# Sheet1.net
KiCad netlist of a schematic drawn in Altium Designer
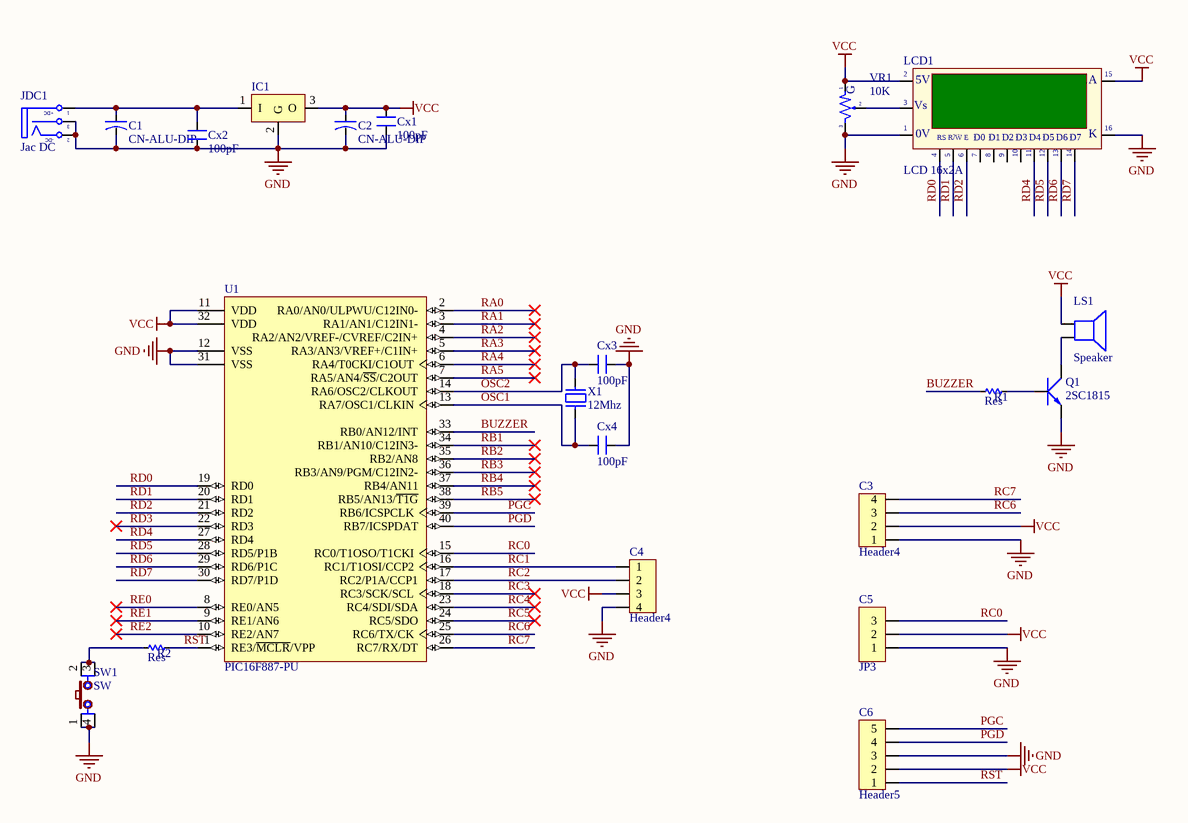
[diagram p0: Sheet1.schdoc]

(export (version "E")
  (design (tool "Eeschema 10.0.6"))
  (components
    (comp (ref "C1")
      (value "CN-ALU-DIP")
      (footprint "CA-ALU-10BL")
      (description "Capacitor (Semiconductor SIM Model)")
      (fields (field (name "PUBLISHER") "Altium Limited"))
      (libsource (lib "Thư Viện Altium FULL HD") (part "CN-ALU-DIP"))
    )
    (comp (ref "C2")
      (value "CN-ALU-DIP")
      (footprint "CA-ALU-10BL")
      (description "Capacitor (Semiconductor SIM Model)")
      (fields (field (name "PUBLISHER") "Altium Limited"))
      (libsource (lib "Thư Viện Altium FULL HD") (part "CN-ALU-DIP"))
    )
    (comp (ref "C3")
      (value "Header4")
      (footprint "Header4")
      (description "Header IDC, 4 x 1 Pin Vertical 2.54mm Pitch (Non-Boxed, Male)")
      (fields
        (field (name "MANUFACTURER") "Würth Elektronik eiSos GmbH")
        (field (name "PARTNO") "613002143121")
        (field (name "CREATED BY") "Karrer Zheng")
      )
      (libsource (lib "Thư Viện Altium FULL HD") (part "Header4"))
    )
    (comp (ref "C4")
      (value "Header4")
      (footprint "Header4")
      (description "Header IDC, 4 x 1 Pin Vertical 2.54mm Pitch (Non-Boxed, Male)")
      (fields
        (field (name "MANUFACTURER") "Würth Elektronik eiSos GmbH")
        (field (name "PARTNO") "613002143121")
        (field (name "CREATED BY") "Karrer Zheng")
      )
      (libsource (lib "") (part "Header4_1"))
    )
    (comp (ref "C5")
      (value "JP3")
      (footprint "JP3-D1T")
      (description "WR-PHD 2.54 mm Angled Socket Header")
      (fields
        (field (name "MANUFACTURER") "Würth Elektronik eiSos GmbH")
        (field (name "PARTNO") "613003143121")
        (field (name "CREATED BY") "Karrer Zheng")
      )
      (libsource (lib "Thư Viện Altium FULL HD") (part "JP3"))
    )
    (comp (ref "C6")
      (value "Header5")
      (footprint "Header5")
      (description "Header IDC, 5 x 1 Pin Vertical 2.54mm Pitch (Non-Boxed, Male)")
      (fields
        (field (name "MANUFACTURER") "Würth Elektronik eiSos GmbH")
        (field (name "PARTNO") "613002143121")
        (field (name "CREATED BY") "Karrer Zheng")
      )
      (libsource (lib "Thư Viện Altium FULL HD") (part "Header5"))
    )
    (comp (ref "Cx1")
      (value "100pF")
      (footprint "CN1.5")
      (libsource (lib "Thư Viện Altium FULL HD") (part "CN"))
    )
    (comp (ref "Cx2")
      (value "100pF")
      (footprint "CN1.5")
      (libsource (lib "Thư Viện Altium FULL HD") (part "CN"))
    )
    (comp (ref "Cx3")
      (value "100pF")
      (footprint "CN2.5")
      (libsource (lib "Thư Viện Altium FULL HD") (part "CN"))
    )
    (comp (ref "Cx4")
      (value "100pF")
      (footprint "CN2.5")
      (libsource (lib "Thư Viện Altium FULL HD") (part "CN"))
    )
    (comp (ref "IC1")
      (value "LM78xx")
      (footprint "TO220-123")
      (description "Positive Voltage Regulator")
      (fields (field (name "PUBLISHER") "Altium Limited"))
      (libsource (lib "Thư Viện Altium FULL HD") (part "LM78xx"))
    )
    (comp (ref "JDC1")
      (value "Jac DC")
      (footprint "DC0")
      (description "Jac DC input")
      (libsource (lib "Thư Viện Altium FULL HD") (part "DCIN"))
    )
    (comp (ref "LCD1")
      (value "LCD 16x2A")
      (footprint "LCD16X2N")
      (description "LCD dipslay 16 char, 2 line")
      (libsource (lib "Thư Viện Altium FULL HD") (part "LCD16x2A"))
    )
    (comp (ref "LS1")
      (value "Speaker")
      (footprint "SPEAKER")
      (description "Loudspeaker")
      (fields (field (name "PUBLISHER") "Altium Limited"))
      (libsource (lib "Thư Viện Altium FULL HD") (part "Speaker"))
    )
    (comp (ref "Q1")
      (value "2SC1815")
      (footprint "TO92-123")
      (description "NPN 600mW, ECB")
      (libsource (lib "Thư Viện Altium FULL HD") (part "2SC1815"))
    )
    (comp (ref "R1")
      (value "Res")
      (footprint "RES-1/4W")
      (fields
        (field (name "MANUFACTURER") "Generic Components")
        (field (name "PUBLISHER") "Altium Hobart Technology Centre")
      )
      (libsource (lib "Thư Viện Altium FULL HD") (part "Res"))
    )
    (comp (ref "R2")
      (value "Res")
      (footprint "RES-1/4W")
      (fields
        (field (name "MANUFACTURER") "Generic Components")
        (field (name "PUBLISHER") "Altium Hobart Technology Centre")
      )
      (libsource (lib "Thư Viện Altium FULL HD") (part "Res"))
    )
    (comp (ref "SW1")
      (value "SW")
      (footprint "SW2-DIP")
      (description "Switch button 4 pin")
      (libsource (lib "Thư Viện Altium FULL HD") (part "SW4"))
    )
    (comp (ref "U1")
      (value "PIC16F887-PU")
      (footprint "DIP40/W0.6")
      (fields (field (name "PUBLISHER") "Altium Limited"))
      (libsource (lib "Thư Viện Altium FULL HD") (part "PIC16F887-PU"))
    )
    (comp (ref "VR1")
      (value "10K")
      (footprint "VR-S2")
      (description "Var Resistor")
      (libsource (lib "Thư Viện Altium FULL HD") (part "VR-S"))
    )
    (comp (ref "X1")
      (value "12Mhz")
      (footprint "XT2")
      (description "Crystal, 32.768 KHz, -40 to 85 degC, 3.2 x 1.5 x 0.9 mm SMD")
      (libsource (lib "Thư Viện Altium FULL HD") (part "XT2"))
    )
  )
  (nets
    (net (code "1") (name "/BUZZER") (class "Default")
      (node (ref "R1") (pin "2") (pinfunction "2_2") (pintype "passive"))
      (node (ref "U1") (pin "33") (pinfunction "RB0/AN12/INT_33") (pintype "bidirectional"))
    )
    (net (code "2") (name "/OSC1") (class "Default")
      (node (ref "Cx4") (pin "1") (pinfunction "1_1") (pintype "passive"))
      (node (ref "U1") (pin "13") (pinfunction "RA7/OSC1/CLKIN_13") (pintype "bidirectional"))
      (node (ref "X1") (pin "1") (pinfunction "1_1") (pintype "passive"))
    )
    (net (code "3") (name "/OSC2") (class "Default")
      (node (ref "Cx3") (pin "1") (pinfunction "1_1") (pintype "passive"))
      (node (ref "U1") (pin "14") (pinfunction "RA6/OSC2/CLKOUT_14") (pintype "bidirectional"))
      (node (ref "X1") (pin "2") (pinfunction "2_2") (pintype "passive"))
    )
    (net (code "4") (name "/PGC") (class "Default")
      (node (ref "C6") (pin "5") (pinfunction "5_5") (pintype "passive"))
      (node (ref "U1") (pin "39") (pinfunction "RB6/ICSPCLK_39") (pintype "bidirectional"))
    )
    (net (code "5") (name "/PGD") (class "Default")
      (node (ref "C6") (pin "4") (pinfunction "4_4") (pintype "passive"))
      (node (ref "U1") (pin "40") (pinfunction "RB7/ICSPDAT_40") (pintype "bidirectional"))
    )
    (net (code "6") (name "/RA0") (class "Default")
      (node (ref "U1") (pin "2") (pinfunction "RA0/AN0/ULPWU/C12IN0-_2") (pintype "bidirectional+no_connect"))
    )
    (net (code "7") (name "/RA1") (class "Default")
      (node (ref "U1") (pin "3") (pinfunction "RA1/AN1/C12IN1-_3") (pintype "bidirectional+no_connect"))
    )
    (net (code "8") (name "/RA2") (class "Default")
      (node (ref "U1") (pin "4") (pinfunction "RA2/AN2/VREF-/CVREF/C2IN+_4") (pintype "bidirectional+no_connect"))
    )
    (net (code "9") (name "/RA3") (class "Default")
      (node (ref "U1") (pin "5") (pinfunction "RA3/AN3/VREF+/C1IN+_5") (pintype "bidirectional+no_connect"))
    )
    (net (code "10") (name "/RA4") (class "Default")
      (node (ref "U1") (pin "6") (pinfunction "RA4/T0CKI/C1OUT_6") (pintype "bidirectional+no_connect"))
    )
    (net (code "11") (name "/RA5") (class "Default")
      (node (ref "U1") (pin "7") (pinfunction "RA5/AN4/~{SS}/C2OUT_7") (pintype "bidirectional+no_connect"))
    )
    (net (code "12") (name "/RB1") (class "Default")
      (node (ref "U1") (pin "34") (pinfunction "RB1/AN10/C12IN3-_34") (pintype "bidirectional+no_connect"))
    )
    (net (code "13") (name "/RB2") (class "Default")
      (node (ref "U1") (pin "35") (pinfunction "RB2/AN8_35") (pintype "bidirectional+no_connect"))
    )
    (net (code "14") (name "/RB3") (class "Default")
      (node (ref "U1") (pin "36") (pinfunction "RB3/AN9/PGM/C12IN2-_36") (pintype "bidirectional+no_connect"))
    )
    (net (code "15") (name "/RB4") (class "Default")
      (node (ref "U1") (pin "37") (pinfunction "RB4/AN11_37") (pintype "bidirectional+no_connect"))
    )
    (net (code "16") (name "/RB5") (class "Default")
      (node (ref "U1") (pin "38") (pinfunction "RB5/AN13/~{T1G}_38") (pintype "bidirectional+no_connect"))
    )
    (net (code "17") (name "/RC0") (class "Default")
      (node (ref "C5") (pin "3") (pinfunction "3_3") (pintype "passive"))
      (node (ref "U1") (pin "15") (pinfunction "RC0/T1OSO/T1CKI_15") (pintype "bidirectional"))
    )
    (net (code "18") (name "/RC1") (class "Default")
      (node (ref "C4") (pin "1") (pinfunction "1_1") (pintype "passive"))
      (node (ref "U1") (pin "16") (pinfunction "RC1/T1OSI/CCP2_16") (pintype "bidirectional"))
    )
    (net (code "19") (name "/RC2") (class "Default")
      (node (ref "C4") (pin "2") (pinfunction "2_2") (pintype "passive"))
      (node (ref "U1") (pin "17") (pinfunction "RC2/P1A/CCP1_17") (pintype "bidirectional"))
    )
    (net (code "20") (name "/RC3") (class "Default")
      (node (ref "U1") (pin "18") (pinfunction "RC3/SCK/SCL_18") (pintype "bidirectional+no_connect"))
    )
    (net (code "21") (name "/RC4") (class "Default")
      (node (ref "U1") (pin "23") (pinfunction "RC4/SDI/SDA_23") (pintype "bidirectional+no_connect"))
    )
    (net (code "22") (name "/RC5") (class "Default")
      (node (ref "U1") (pin "24") (pinfunction "RC5/SDO_24") (pintype "bidirectional+no_connect"))
    )
    (net (code "23") (name "/RC6") (class "Default")
      (node (ref "C3") (pin "3") (pinfunction "3_3") (pintype "passive"))
      (node (ref "U1") (pin "25") (pinfunction "RC6/TX/CK_25") (pintype "bidirectional"))
    )
    (net (code "24") (name "/RC7") (class "Default")
      (node (ref "C3") (pin "4") (pinfunction "4_4") (pintype "passive"))
      (node (ref "U1") (pin "26") (pinfunction "RC7/RX/DT_26") (pintype "bidirectional"))
    )
    (net (code "25") (name "/RD0") (class "Default")
      (node (ref "LCD1") (pin "4") (pinfunction "RS_4") (pintype "passive"))
      (node (ref "U1") (pin "19") (pinfunction "RD0_19") (pintype "bidirectional"))
    )
    (net (code "26") (name "/RD1") (class "Default")
      (node (ref "LCD1") (pin "5") (pinfunction "R/~{W}_5") (pintype "passive"))
      (node (ref "U1") (pin "20") (pinfunction "RD1_20") (pintype "bidirectional"))
    )
    (net (code "27") (name "/RD2") (class "Default")
      (node (ref "LCD1") (pin "6") (pinfunction "~{EN}_6") (pintype "passive"))
      (node (ref "U1") (pin "21") (pinfunction "RD2_21") (pintype "bidirectional"))
    )
    (net (code "28") (name "/RD3") (class "Default")
      (node (ref "U1") (pin "22") (pinfunction "RD3_22") (pintype "bidirectional+no_connect"))
    )
    (net (code "29") (name "/RD4") (class "Default")
      (node (ref "LCD1") (pin "11") (pinfunction "D4_11") (pintype "passive"))
      (node (ref "U1") (pin "27") (pinfunction "RD4_27") (pintype "bidirectional"))
    )
    (net (code "30") (name "/RD5") (class "Default")
      (node (ref "LCD1") (pin "12") (pinfunction "D5_12") (pintype "passive"))
      (node (ref "U1") (pin "28") (pinfunction "RD5/P1B_28") (pintype "bidirectional"))
    )
    (net (code "31") (name "/RD6") (class "Default")
      (node (ref "LCD1") (pin "13") (pinfunction "D6_13") (pintype "passive"))
      (node (ref "U1") (pin "29") (pinfunction "RD6/P1C_29") (pintype "bidirectional"))
    )
    (net (code "32") (name "/RD7") (class "Default")
      (node (ref "LCD1") (pin "14") (pinfunction "D7_14") (pintype "passive"))
      (node (ref "U1") (pin "30") (pinfunction "RD7/P1D_30") (pintype "bidirectional"))
    )
    (net (code "33") (name "/RE0") (class "Default")
      (node (ref "U1") (pin "8") (pinfunction "RE0/AN5_8") (pintype "bidirectional+no_connect"))
    )
    (net (code "34") (name "/RE1") (class "Default")
      (node (ref "U1") (pin "9") (pinfunction "RE1/AN6_9") (pintype "bidirectional+no_connect"))
    )
    (net (code "35") (name "/RE2") (class "Default")
      (node (ref "U1") (pin "10") (pinfunction "RE2/AN7_10") (pintype "bidirectional+no_connect"))
    )
    (net (code "36") (name "/RST") (class "Default")
      (node (ref "C6") (pin "1") (pinfunction "1_1") (pintype "passive"))
      (node (ref "R2") (pin "1") (pinfunction "1_1") (pintype "passive"))
      (node (ref "U1") (pin "1") (pinfunction "RE3/~{MCLR}/VPP_1") (pintype "bidirectional"))
    )
    (net (code "37") (name "GND") (class "Default")
      (node (ref "C1") (pin "2") (pinfunction "2_2") (pintype "passive"))
      (node (ref "C2") (pin "2") (pinfunction "2_2") (pintype "passive"))
      (node (ref "C3") (pin "1") (pinfunction "1_1") (pintype "passive"))
      (node (ref "C4") (pin "4") (pinfunction "4_4") (pintype "passive"))
      (node (ref "C5") (pin "1") (pinfunction "1_1") (pintype "passive"))
      (node (ref "C6") (pin "3") (pinfunction "3_3") (pintype "passive"))
      (node (ref "Cx1") (pin "2") (pinfunction "2_2") (pintype "passive"))
      (node (ref "Cx2") (pin "2") (pinfunction "2_2") (pintype "passive"))
      (node (ref "Cx3") (pin "2") (pinfunction "2_2") (pintype "passive"))
      (node (ref "Cx4") (pin "2") (pinfunction "2_2") (pintype "passive"))
      (node (ref "IC1") (pin "2") (pinfunction "G_2") (pintype "power_in"))
      (node (ref "JDC1") (pin "2") (pinfunction "TN_2") (pintype "passive"))
      (node (ref "JDC1") (pin "3") (pinfunction "S_3") (pintype "power_in"))
      (node (ref "LCD1") (pin "1") (pinfunction "GND_1") (pintype "passive"))
      (node (ref "LCD1") (pin "16") (pinfunction "K_16") (pintype "passive"))
      (node (ref "Q1") (pin "1") (pinfunction "E_1") (pintype "passive"))
      (node (ref "SW1") (pin "1") (pintype "passive"))
      (node (ref "SW1") (pin "4") (pinfunction "4_4") (pintype "passive"))
      (node (ref "U1") (pin "12") (pinfunction "VSS_12") (pintype "power_in"))
      (node (ref "U1") (pin "31") (pinfunction "VSS_31") (pintype "power_in"))
      (node (ref "VR1") (pin "3") (pinfunction "3_3") (pintype "passive"))
    )
    (net (code "38") (name "Net-(IC1-I)") (class "Default")
      (node (ref "C1") (pin "1") (pinfunction "1_1") (pintype "passive"))
      (node (ref "Cx2") (pin "1") (pinfunction "1_1") (pintype "passive"))
      (node (ref "IC1") (pin "1") (pinfunction "I_1") (pintype "power_in"))
      (node (ref "JDC1") (pin "1") (pinfunction "T_1") (pintype "passive"))
    )
    (net (code "39") (name "Net-(LCD1-VEE)") (class "Default")
      (node (ref "LCD1") (pin "3") (pinfunction "VEE_3") (pintype "passive"))
      (node (ref "VR1") (pin "2") (pinfunction "2_2") (pintype "passive"))
    )
    (net (code "40") (name "Net-(Q1-B)") (class "Default")
      (node (ref "Q1") (pin "3") (pinfunction "B_3") (pintype "passive"))
      (node (ref "R1") (pin "1") (pinfunction "1_1") (pintype "passive"))
    )
    (net (code "41") (name "Net-(Q1-C)") (class "Default")
      (node (ref "LS1") (pin "2") (pinfunction "2_2") (pintype "passive"))
      (node (ref "Q1") (pin "2") (pinfunction "C_2") (pintype "passive"))
    )
    (net (code "42") (name "Net-(R2-Pad2)") (class "Default")
      (node (ref "R2") (pin "2") (pinfunction "2_2") (pintype "passive"))
      (node (ref "SW1") (pin "2") (pinfunction "2_2") (pintype "passive"))
      (node (ref "SW1") (pin "3") (pinfunction "3_3") (pintype "passive"))
    )
    (net (code "43") (name "VCC") (class "Default")
      (node (ref "C2") (pin "1") (pinfunction "1_1") (pintype "passive"))
      (node (ref "C3") (pin "2") (pinfunction "2_2") (pintype "passive"))
      (node (ref "C4") (pin "3") (pinfunction "3_3") (pintype "passive"))
      (node (ref "C5") (pin "2") (pinfunction "2_2") (pintype "passive"))
      (node (ref "C6") (pin "2") (pinfunction "2_2") (pintype "passive"))
      (node (ref "Cx1") (pin "1") (pinfunction "1_1") (pintype "passive"))
      (node (ref "IC1") (pin "3") (pinfunction "O_3") (pintype "power_in"))
      (node (ref "LCD1") (pin "15") (pinfunction "A_15") (pintype "passive"))
      (node (ref "LCD1") (pin "2") (pinfunction "VDD_2") (pintype "passive"))
      (node (ref "LS1") (pin "1") (pinfunction "1_1") (pintype "passive"))
      (node (ref "U1") (pin "11") (pinfunction "VDD_11") (pintype "power_in"))
      (node (ref "U1") (pin "32") (pinfunction "VDD_32") (pintype "power_in"))
      (node (ref "VR1") (pin "1") (pinfunction "1_1") (pintype "passive"))
    )
    (net (code "44") (name "unconnected-(LCD1-D0-Pad7)") (class "Default")
      (node (ref "LCD1") (pin "7") (pinfunction "D0_7") (pintype "passive"))
    )
    (net (code "45") (name "unconnected-(LCD1-D1-Pad8)") (class "Default")
      (node (ref "LCD1") (pin "8") (pinfunction "D1_8") (pintype "passive"))
    )
    (net (code "46") (name "unconnected-(LCD1-D2-Pad9)") (class "Default")
      (node (ref "LCD1") (pin "9") (pinfunction "D2_9") (pintype "passive"))
    )
    (net (code "47") (name "unconnected-(LCD1-D3-Pad10)") (class "Default")
      (node (ref "LCD1") (pin "10") (pinfunction "D3_10") (pintype "passive"))
    )
  )
)
